# Full_Wave_Bridge_Rectifier.net
KiCad netlist of a schematic drawn in EasyEDA Pro
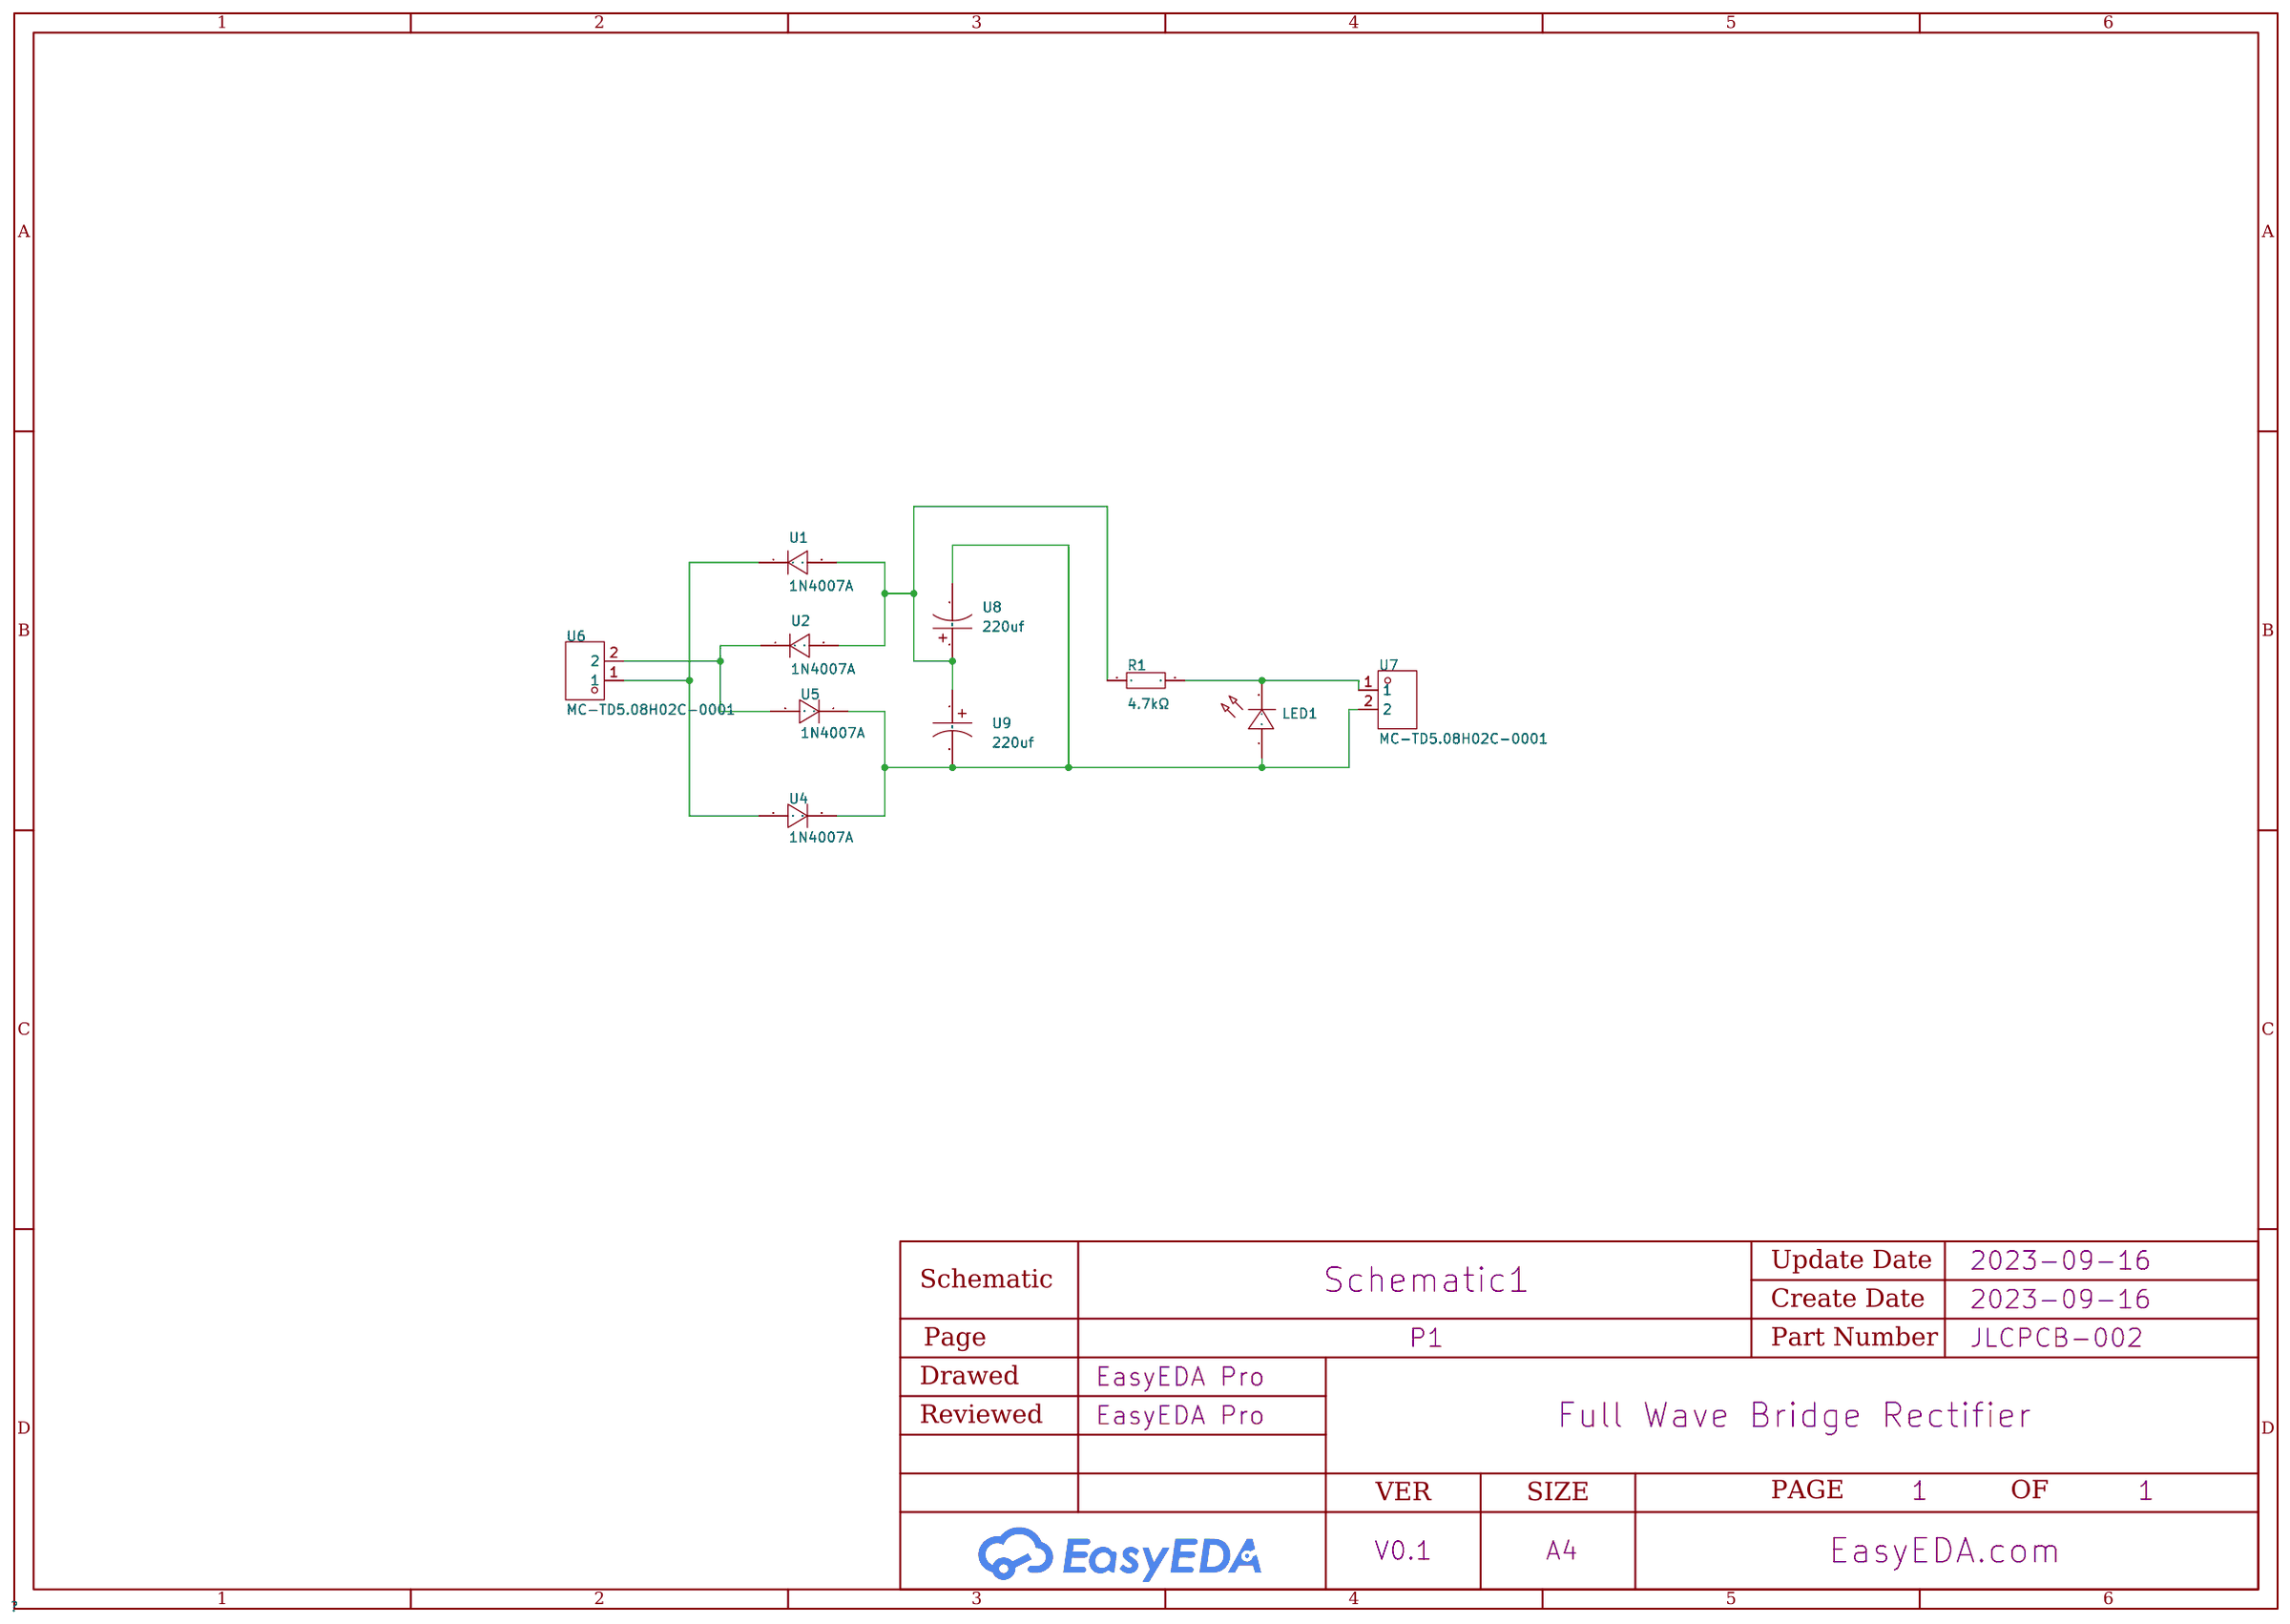
[diagram p0: schematic sheet]

(export (version "E")
  (design (tool "Eeschema 10.0.6"))
  (components
    (comp (ref "LED1")
      (value "~")
      (footprint "easyedapro:LED-TH_BD3.0-P2.54-FD")
      (libsource (lib "easyedapro") (part "LED_TH-R"))
    )
    (comp (ref "R1")
      (value "4.7kΩ")
      (footprint "easyedapro:RES-TH_BD1.8-L3.2-P7.20-D0.4")
      (libsource (lib "easyedapro") (part "Res"))
    )
    (comp (ref "U1")
      (value "1N4007A")
      (footprint "easyedapro:DO-41_BD2.4-L4.7-P8.70-D0.9-RD")
      (fields (field (name "Manufacturer") "LRC(乐山无线电)"))
      (libsource (lib "easyedapro") (part "1N4007A"))
    )
    (comp (ref "U2")
      (value "1N4007A")
      (footprint "easyedapro:DO-41_BD2.4-L4.7-P8.70-D0.9-RD")
      (fields (field (name "Manufacturer") "LRC(乐山无线电)"))
      (libsource (lib "easyedapro") (part "1N4007A"))
    )
    (comp (ref "U4")
      (value "1N4007A")
      (footprint "easyedapro:DO-41_BD2.4-L4.7-P8.70-D0.9-RD")
      (fields (field (name "Manufacturer") "LRC(乐山无线电)"))
      (libsource (lib "easyedapro") (part "1N4007A"))
    )
    (comp (ref "U5")
      (value "1N4007A")
      (footprint "easyedapro:DO-41_BD2.4-L4.7-P8.70-D0.9-RD")
      (fields (field (name "Manufacturer") "LRC(乐山无线电)"))
      (libsource (lib "easyedapro") (part "1N4007A"))
    )
    (comp (ref "U6")
      (value "MC-TD5.08H02C-0001")
      (footprint "easyedapro:CONN-TH_MC-TD5.08H02C-0001")
      (fields (field (name "Manufacturer") "SUPU(速普)"))
      (libsource (lib "easyedapro") (part "MC-TD5.08H02C-0001"))
    )
    (comp (ref "U7")
      (value "MC-TD5.08H02C-0001")
      (footprint "easyedapro:CONN-TH_MC-TD5.08H02C-0001")
      (fields (field (name "Manufacturer") "SUPU(速普)"))
      (libsource (lib "easyedapro") (part "MC-TD5.08H02C-0001"))
    )
    (comp (ref "U8")
      (value "220uf")
      (footprint "easyedapro:CAP-TH_BD8.0-P3.50-D0.6-FD")
      (libsource (lib "easyedapro") (part "CAPACITOR_THT{colon}CP_RADIAL_D8.0MM_P2.50MM"))
    )
    (comp (ref "U9")
      (value "220uf")
      (footprint "easyedapro:CAP-TH_BD8.0-P3.50-D0.6-FD")
      (libsource (lib "easyedapro") (part "CAPACITOR_THT{colon}CP_RADIAL_D8.0MM_P2.50MM"))
    )
  )
  (nets
    (net (code "1") (name "Net-(LED1-A)") (class "Default")
      (node (ref "LED1") (pin "2") (pinfunction "A_2") (pintype "input"))
      (node (ref "R1") (pin "2") (pinfunction "2_2") (pintype "input"))
      (node (ref "U7") (pin "1") (pinfunction "1_1") (pintype "input"))
    )
    (net (code "2") (name "Net-(LED1-C)") (class "Default")
      (node (ref "LED1") (pin "1") (pinfunction "C_1") (pintype "input"))
      (node (ref "U4") (pin "1") (pinfunction "1_1") (pintype "input"))
      (node (ref "U5") (pin "1") (pinfunction "1_1") (pintype "input"))
      (node (ref "U7") (pin "2") (pinfunction "2_2") (pintype "input"))
      (node (ref "U8") (pin "2") (pinfunction "2_2") (pintype "input"))
      (node (ref "U9") (pin "2") (pinfunction "2_2") (pintype "input"))
    )
    (net (code "3") (name "Net-(R1-Pad1)") (class "Default")
      (node (ref "R1") (pin "1") (pinfunction "1_1") (pintype "input"))
      (node (ref "U1") (pin "2") (pinfunction "2_2") (pintype "input"))
      (node (ref "U2") (pin "2") (pinfunction "2_2") (pintype "input"))
      (node (ref "U8") (pin "1") (pinfunction "1_1") (pintype "input"))
      (node (ref "U9") (pin "1") (pinfunction "1_1") (pintype "input"))
    )
    (net (code "4") (name "Net-(U1-Pad1)") (class "Default")
      (node (ref "U1") (pin "1") (pinfunction "1_1") (pintype "input"))
      (node (ref "U4") (pin "2") (pinfunction "2_2") (pintype "input"))
      (node (ref "U6") (pin "1") (pinfunction "1_1") (pintype "input"))
    )
    (net (code "5") (name "Net-(U2-Pad1)") (class "Default")
      (node (ref "U2") (pin "1") (pinfunction "1_1") (pintype "input"))
      (node (ref "U5") (pin "2") (pinfunction "2_2") (pintype "input"))
      (node (ref "U6") (pin "2") (pinfunction "2_2") (pintype "input"))
    )
  )
)
